# Output_Contactor.net
KiCad netlist of a schematic drawn in Altium Designer
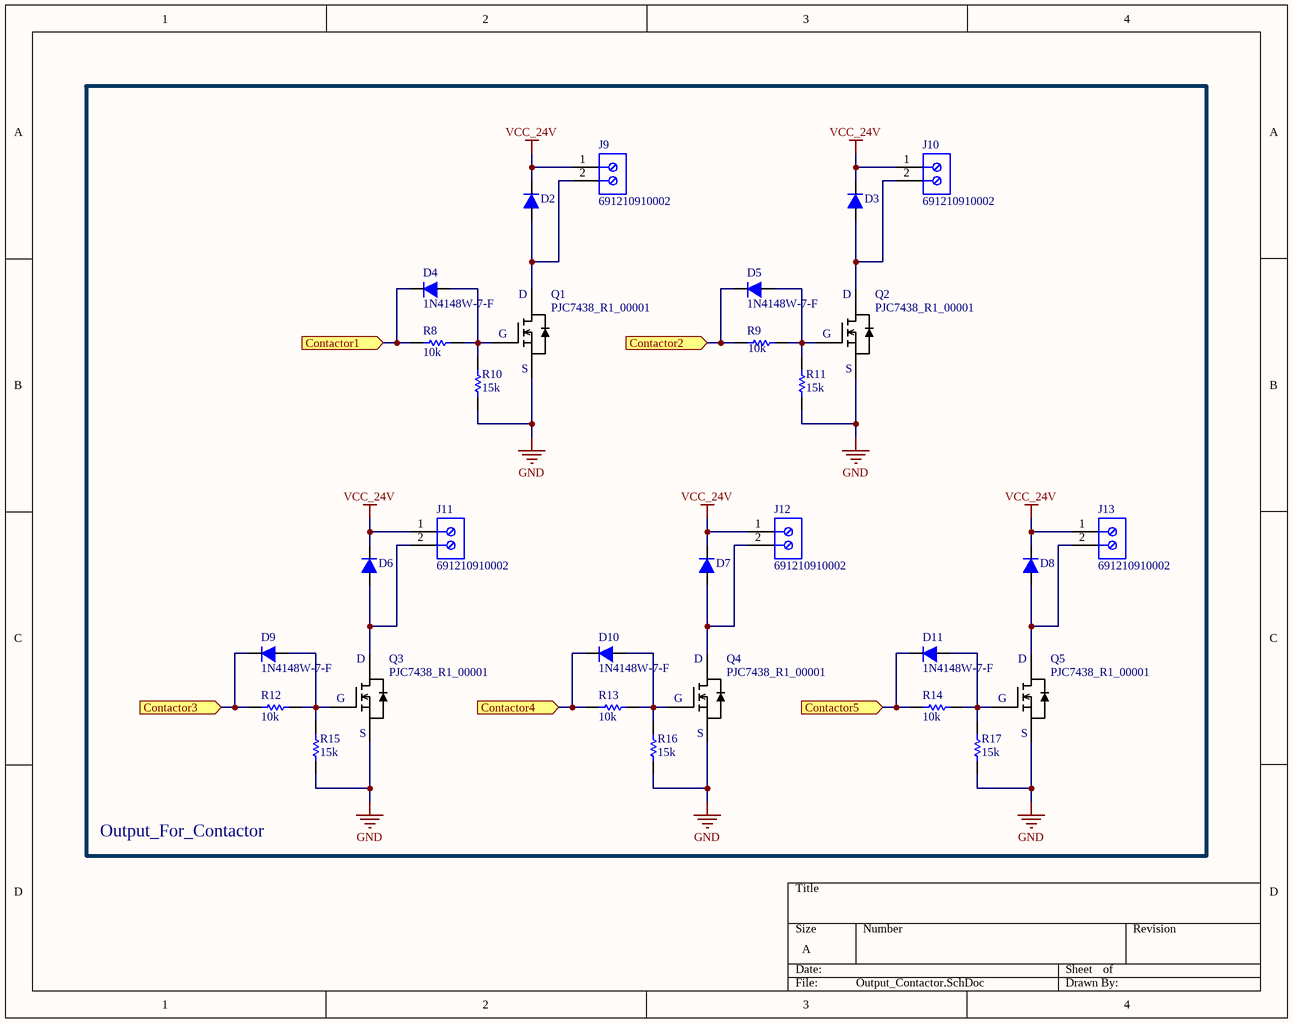
[diagram p0: Output_Contactor.SchDoc]

(export (version "E")
  (design (tool "Eeschema 10.0.6"))
  (components
    (comp (ref "D2")
      (value "US1A-13-F")
      (footprint "US1A-13-F")
      (description "Diode Standard 50 V 1A Surface Mount SMA")
      (fields (field (name "MFR") "Diodes Incorporated"))
      (libsource (lib "Integrated_Library1") (part "US1A-13-F"))
    )
    (comp (ref "D3")
      (value "US1A-13-F")
      (footprint "US1A-13-F")
      (description "Diode Standard 50 V 1A Surface Mount SMA")
      (fields (field (name "MFR") "Diodes Incorporated"))
      (libsource (lib "Integrated_Library1") (part "US1A-13-F"))
    )
    (comp (ref "D4")
      (value "1N4148W-7-F")
      (footprint "1N4148")
      (description "Diode Standard 100 V 300mA (DC) Surface Mount SOD-123")
      (fields (field (name "MFR") "Diodes Incorporated"))
      (libsource (lib "Integrated_Library1") (part "1N4148"))
    )
    (comp (ref "D5")
      (value "1N4148W-7-F")
      (footprint "1N4148")
      (description "Diode Standard 100 V 300mA (DC) Surface Mount SOD-123")
      (fields (field (name "MFR") "Diodes Incorporated"))
      (libsource (lib "Integrated_Library1") (part "1N4148"))
    )
    (comp (ref "D6")
      (value "US1A-13-F")
      (footprint "US1A-13-F")
      (description "Diode Standard 50 V 1A Surface Mount SMA")
      (fields (field (name "MFR") "Diodes Incorporated"))
      (libsource (lib "Integrated_Library1") (part "US1A-13-F"))
    )
    (comp (ref "D7")
      (value "US1A-13-F")
      (footprint "US1A-13-F")
      (description "Diode Standard 50 V 1A Surface Mount SMA")
      (fields (field (name "MFR") "Diodes Incorporated"))
      (libsource (lib "Integrated_Library1") (part "US1A-13-F"))
    )
    (comp (ref "D8")
      (value "US1A-13-F")
      (footprint "US1A-13-F")
      (description "Diode Standard 50 V 1A Surface Mount SMA")
      (fields (field (name "MFR") "Diodes Incorporated"))
      (libsource (lib "Integrated_Library1") (part "US1A-13-F"))
    )
    (comp (ref "D9")
      (value "1N4148W-7-F")
      (footprint "1N4148")
      (description "Diode Standard 100 V 300mA (DC) Surface Mount SOD-123")
      (fields (field (name "MFR") "Diodes Incorporated"))
      (libsource (lib "Integrated_Library1") (part "1N4148"))
    )
    (comp (ref "D10")
      (value "1N4148W-7-F")
      (footprint "1N4148")
      (description "Diode Standard 100 V 300mA (DC) Surface Mount SOD-123")
      (fields (field (name "MFR") "Diodes Incorporated"))
      (libsource (lib "Integrated_Library1") (part "1N4148"))
    )
    (comp (ref "D11")
      (value "1N4148W-7-F")
      (footprint "1N4148")
      (description "Diode Standard 100 V 300mA (DC) Surface Mount SOD-123")
      (fields (field (name "MFR") "Diodes Incorporated"))
      (libsource (lib "Integrated_Library1") (part "1N4148"))
    )
    (comp (ref "J9")
      (value "691210910002")
      (footprint "691210910002")
      (description "WR-TBL Serie 2109 Horizontal Entry, Rising Cage Clamp, pitch 2.54mm, 2p")
      (fields (field (name "PUBLISHER") "Wurth Elektronik"))
      (libsource (lib "691322310002.") (part "691210910002"))
    )
    (comp (ref "J10")
      (value "691210910002")
      (footprint "691210910002")
      (description "WR-TBL Serie 2109 Horizontal Entry, Rising Cage Clamp, pitch 2.54mm, 2p")
      (fields (field (name "PUBLISHER") "Wurth Elektronik"))
      (libsource (lib "691322310002.") (part "691210910002"))
    )
    (comp (ref "J11")
      (value "691210910002")
      (footprint "691210910002")
      (description "WR-TBL Serie 2109 Horizontal Entry, Rising Cage Clamp, pitch 2.54mm, 2p")
      (fields (field (name "PUBLISHER") "Wurth Elektronik"))
      (libsource (lib "691322310002.") (part "691210910002"))
    )
    (comp (ref "J12")
      (value "691210910002")
      (footprint "691210910002")
      (description "WR-TBL Serie 2109 Horizontal Entry, Rising Cage Clamp, pitch 2.54mm, 2p")
      (fields (field (name "PUBLISHER") "Wurth Elektronik"))
      (libsource (lib "691322310002.") (part "691210910002"))
    )
    (comp (ref "J13")
      (value "691210910002")
      (footprint "691210910002")
      (description "WR-TBL Serie 2109 Horizontal Entry, Rising Cage Clamp, pitch 2.54mm, 2p")
      (fields (field (name "PUBLISHER") "Wurth Elektronik"))
      (libsource (lib "691322310002.") (part "691210910002"))
    )
    (comp (ref "Q1")
      (value "PJC7438_R1_00001")
      (footprint "PJC7438")
      (description "N-Channel 50 V 400mA (Ta) 350mW (Ta) Surface Mount SOT-323")
      (fields (field (name "MFR") "Panjit International Inc."))
      (libsource (lib "Integrated_Library1") (part "PJC7438"))
    )
    (comp (ref "Q2")
      (value "PJC7438_R1_00001")
      (footprint "PJC7438")
      (description "N-Channel 50 V 400mA (Ta) 350mW (Ta) Surface Mount SOT-323")
      (fields (field (name "MFR") "Panjit International Inc."))
      (libsource (lib "Integrated_Library1") (part "PJC7438"))
    )
    (comp (ref "Q3")
      (value "PJC7438_R1_00001")
      (footprint "PJC7438")
      (description "N-Channel 50 V 400mA (Ta) 350mW (Ta) Surface Mount SOT-323")
      (fields (field (name "MFR") "Panjit International Inc."))
      (libsource (lib "Integrated_Library1") (part "PJC7438"))
    )
    (comp (ref "Q4")
      (value "PJC7438_R1_00001")
      (footprint "PJC7438")
      (description "N-Channel 50 V 400mA (Ta) 350mW (Ta) Surface Mount SOT-323")
      (fields (field (name "MFR") "Panjit International Inc."))
      (libsource (lib "Integrated_Library1") (part "PJC7438"))
    )
    (comp (ref "Q5")
      (value "PJC7438_R1_00001")
      (footprint "PJC7438")
      (description "N-Channel 50 V 400mA (Ta) 350mW (Ta) Surface Mount SOT-323")
      (fields (field (name "MFR") "Panjit International Inc."))
      (libsource (lib "Integrated_Library1") (part "PJC7438"))
    )
    (comp (ref "R8")
      (value "10k")
      (footprint "RES-SM-0603")
      (description "RES SMD 10K OHM 1% 1/4W 0603")
      (fields (field (name "MFR") "Rohm Semiconductor") (field (name "TOLERANCE") "±1%"))
      (libsource (lib "PIF_Library") (part "RESISTOR SMD"))
    )
    (comp (ref "R9")
      (value "10k")
      (footprint "RES-SM-0603")
      (description "RES SMD 10K OHM 1% 1/4W 0603")
      (fields (field (name "MFR") "Rohm Semiconductor") (field (name "TOLERANCE") "±1%"))
      (libsource (lib "PIF_Library") (part "RESISTOR SMD"))
    )
    (comp (ref "R10")
      (value "15k")
      (footprint "RES-SM-0603")
      (description "RES SMD 15K OHM 5% 1/4W 0603")
      (fields (field (name "MFR") "Rohm Semiconductor") (field (name "TOLERANCE") "±5%"))
      (libsource (lib "PIF_Library") (part "RESISTOR SMD"))
    )
    (comp (ref "R11")
      (value "15k")
      (footprint "RES-SM-0603")
      (description "RES SMD 15K OHM 5% 1/4W 0603")
      (fields (field (name "MFR") "Rohm Semiconductor") (field (name "TOLERANCE") "±5%"))
      (libsource (lib "PIF_Library") (part "RESISTOR SMD"))
    )
    (comp (ref "R12")
      (value "10k")
      (footprint "RES-SM-0603")
      (description "RES SMD 10K OHM 1% 1/4W 0603")
      (fields (field (name "MFR") "Rohm Semiconductor") (field (name "TOLERANCE") "±1%"))
      (libsource (lib "PIF_Library") (part "RESISTOR SMD"))
    )
    (comp (ref "R13")
      (value "10k")
      (footprint "RES-SM-0603")
      (description "RES SMD 10K OHM 1% 1/4W 0603")
      (fields (field (name "MFR") "Rohm Semiconductor") (field (name "TOLERANCE") "±1%"))
      (libsource (lib "PIF_Library") (part "RESISTOR SMD"))
    )
    (comp (ref "R14")
      (value "10k")
      (footprint "RES-SM-0603")
      (description "RES SMD 10K OHM 1% 1/4W 0603")
      (fields (field (name "MFR") "Rohm Semiconductor") (field (name "TOLERANCE") "±1%"))
      (libsource (lib "PIF_Library") (part "RESISTOR SMD"))
    )
    (comp (ref "R15")
      (value "15k")
      (footprint "RES-SM-0603")
      (description "RES SMD 15K OHM 5% 1/4W 0603")
      (fields (field (name "MFR") "Rohm Semiconductor") (field (name "TOLERANCE") "±5%"))
      (libsource (lib "PIF_Library") (part "RESISTOR SMD"))
    )
    (comp (ref "R16")
      (value "15k")
      (footprint "RES-SM-0603")
      (description "RES SMD 15K OHM 5% 1/4W 0603")
      (fields (field (name "MFR") "Rohm Semiconductor") (field (name "TOLERANCE") "±5%"))
      (libsource (lib "PIF_Library") (part "RESISTOR SMD"))
    )
    (comp (ref "R17")
      (value "15k")
      (footprint "RES-SM-0603")
      (description "RES SMD 15K OHM 5% 1/4W 0603")
      (fields (field (name "MFR") "Rohm Semiconductor") (field (name "TOLERANCE") "±5%"))
      (libsource (lib "PIF_Library") (part "RESISTOR SMD"))
    )
  )
  (nets
    (net (code "1") (name "/Contactor1") (class "Default")
      (node (ref "D4") (pin "2") (pinfunction "K_2") (pintype "passive"))
      (node (ref "R8") (pin "2") (pinfunction "2_2") (pintype "passive"))
    )
    (net (code "2") (name "/Contactor2") (class "Default")
      (node (ref "D5") (pin "2") (pinfunction "K_2") (pintype "passive"))
      (node (ref "R9") (pin "2") (pinfunction "2_2") (pintype "passive"))
    )
    (net (code "3") (name "/Contactor3") (class "Default")
      (node (ref "D9") (pin "2") (pinfunction "K_2") (pintype "passive"))
      (node (ref "R12") (pin "2") (pinfunction "2_2") (pintype "passive"))
    )
    (net (code "4") (name "/Contactor4") (class "Default")
      (node (ref "D10") (pin "2") (pinfunction "K_2") (pintype "passive"))
      (node (ref "R13") (pin "2") (pinfunction "2_2") (pintype "passive"))
    )
    (net (code "5") (name "/Contactor5") (class "Default")
      (node (ref "D11") (pin "2") (pinfunction "K_2") (pintype "passive"))
      (node (ref "R14") (pin "2") (pinfunction "2_2") (pintype "passive"))
    )
    (net (code "6") (name "GND") (class "Default")
      (node (ref "Q1") (pin "2") (pinfunction "S_2") (pintype "passive"))
      (node (ref "Q2") (pin "2") (pinfunction "S_2") (pintype "passive"))
      (node (ref "Q3") (pin "2") (pinfunction "S_2") (pintype "passive"))
      (node (ref "Q4") (pin "2") (pinfunction "S_2") (pintype "passive"))
      (node (ref "Q5") (pin "2") (pinfunction "S_2") (pintype "passive"))
      (node (ref "R10") (pin "2") (pinfunction "2_2") (pintype "passive"))
      (node (ref "R11") (pin "2") (pinfunction "2_2") (pintype "passive"))
      (node (ref "R15") (pin "2") (pinfunction "2_2") (pintype "passive"))
      (node (ref "R16") (pin "2") (pinfunction "2_2") (pintype "passive"))
      (node (ref "R17") (pin "2") (pinfunction "2_2") (pintype "passive"))
    )
    (net (code "7") (name "Net-(D2-A)") (class "Default")
      (node (ref "D2") (pin "1") (pinfunction "A_1") (pintype "passive"))
      (node (ref "J9") (pin "2") (pinfunction "2_2") (pintype "passive"))
      (node (ref "Q1") (pin "3") (pinfunction "D_3") (pintype "passive"))
    )
    (net (code "8") (name "Net-(D3-A)") (class "Default")
      (node (ref "D3") (pin "1") (pinfunction "A_1") (pintype "passive"))
      (node (ref "J10") (pin "2") (pinfunction "2_2") (pintype "passive"))
      (node (ref "Q2") (pin "3") (pinfunction "D_3") (pintype "passive"))
    )
    (net (code "9") (name "Net-(D4-A)") (class "Default")
      (node (ref "D4") (pin "1") (pinfunction "A_1") (pintype "passive"))
      (node (ref "Q1") (pin "1") (pinfunction "G_1") (pintype "passive"))
      (node (ref "R10") (pin "1") (pinfunction "1_1") (pintype "passive"))
      (node (ref "R8") (pin "1") (pinfunction "1_1") (pintype "passive"))
    )
    (net (code "10") (name "Net-(D5-A)") (class "Default")
      (node (ref "D5") (pin "1") (pinfunction "A_1") (pintype "passive"))
      (node (ref "Q2") (pin "1") (pinfunction "G_1") (pintype "passive"))
      (node (ref "R11") (pin "1") (pinfunction "1_1") (pintype "passive"))
      (node (ref "R9") (pin "1") (pinfunction "1_1") (pintype "passive"))
    )
    (net (code "11") (name "Net-(D6-A)") (class "Default")
      (node (ref "D6") (pin "1") (pinfunction "A_1") (pintype "passive"))
      (node (ref "J11") (pin "2") (pinfunction "2_2") (pintype "passive"))
      (node (ref "Q3") (pin "3") (pinfunction "D_3") (pintype "passive"))
    )
    (net (code "12") (name "Net-(D7-A)") (class "Default")
      (node (ref "D7") (pin "1") (pinfunction "A_1") (pintype "passive"))
      (node (ref "J12") (pin "2") (pinfunction "2_2") (pintype "passive"))
      (node (ref "Q4") (pin "3") (pinfunction "D_3") (pintype "passive"))
    )
    (net (code "13") (name "Net-(D8-A)") (class "Default")
      (node (ref "D8") (pin "1") (pinfunction "A_1") (pintype "passive"))
      (node (ref "J13") (pin "2") (pinfunction "2_2") (pintype "passive"))
      (node (ref "Q5") (pin "3") (pinfunction "D_3") (pintype "passive"))
    )
    (net (code "14") (name "Net-(D9-A)") (class "Default")
      (node (ref "D9") (pin "1") (pinfunction "A_1") (pintype "passive"))
      (node (ref "Q3") (pin "1") (pinfunction "G_1") (pintype "passive"))
      (node (ref "R12") (pin "1") (pinfunction "1_1") (pintype "passive"))
      (node (ref "R15") (pin "1") (pinfunction "1_1") (pintype "passive"))
    )
    (net (code "15") (name "Net-(D10-A)") (class "Default")
      (node (ref "D10") (pin "1") (pinfunction "A_1") (pintype "passive"))
      (node (ref "Q4") (pin "1") (pinfunction "G_1") (pintype "passive"))
      (node (ref "R13") (pin "1") (pinfunction "1_1") (pintype "passive"))
      (node (ref "R16") (pin "1") (pinfunction "1_1") (pintype "passive"))
    )
    (net (code "16") (name "Net-(D11-A)") (class "Default")
      (node (ref "D11") (pin "1") (pinfunction "A_1") (pintype "passive"))
      (node (ref "Q5") (pin "1") (pinfunction "G_1") (pintype "passive"))
      (node (ref "R14") (pin "1") (pinfunction "1_1") (pintype "passive"))
      (node (ref "R17") (pin "1") (pinfunction "1_1") (pintype "passive"))
    )
    (net (code "17") (name "VCC_24V") (class "Default")
      (node (ref "D2") (pin "2") (pinfunction "K_2") (pintype "passive"))
      (node (ref "D3") (pin "2") (pinfunction "K_2") (pintype "passive"))
      (node (ref "D6") (pin "2") (pinfunction "K_2") (pintype "passive"))
      (node (ref "D7") (pin "2") (pinfunction "K_2") (pintype "passive"))
      (node (ref "D8") (pin "2") (pinfunction "K_2") (pintype "passive"))
      (node (ref "J10") (pin "1") (pinfunction "1_1") (pintype "passive"))
      (node (ref "J11") (pin "1") (pinfunction "1_1") (pintype "passive"))
      (node (ref "J12") (pin "1") (pinfunction "1_1") (pintype "passive"))
      (node (ref "J13") (pin "1") (pinfunction "1_1") (pintype "passive"))
      (node (ref "J9") (pin "1") (pinfunction "1_1") (pintype "passive"))
    )
  )
)
